# KwadraLampaBT.net
KiCad netlist of a schematic drawn in EAGLE
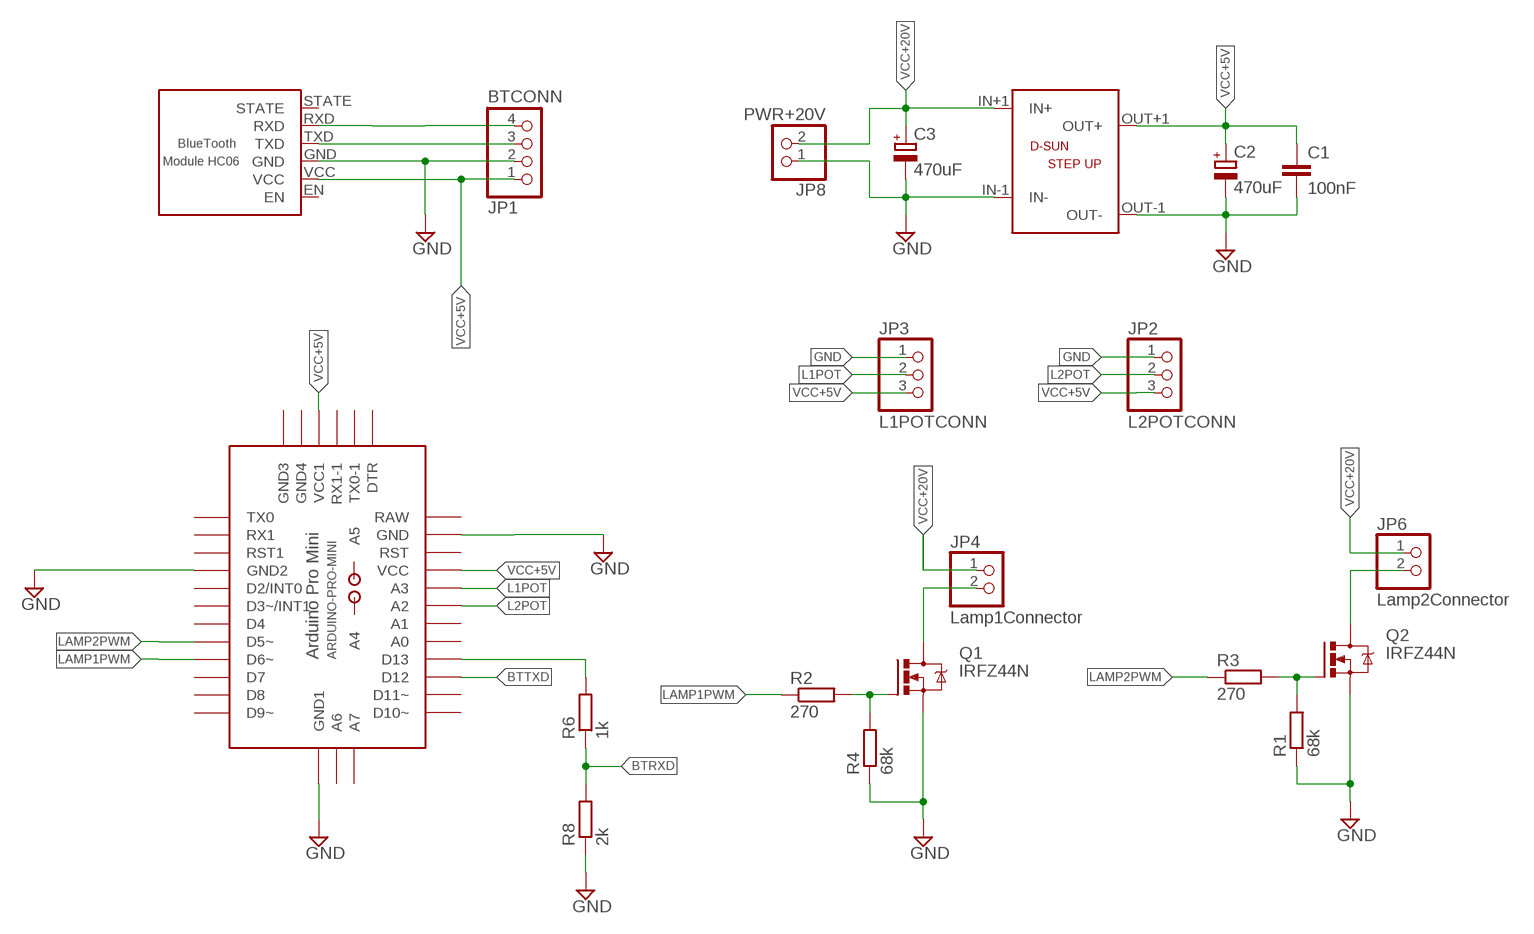
[diagram p0: schematic, sheet 1]

(export (version "E")
  (design (tool "Eeschema 10.0.6"))
  (components
    (comp (ref "C1")
      (value "100nF")
      (footprint "eagle-import:C025-025X050")
      (libsource (lib "eagle-import") (part "C_CERAMIC_2.5X50"))
    )
    (comp (ref "C2")
      (value "470uF")
      (footprint "eagle-import:C_E_R5-FI13_ELECTROLYTIC")
      (libsource (lib "eagle-import") (part "C_ELECTROLYTIC_3"))
    )
    (comp (ref "C3")
      (value "470uF")
      (footprint "eagle-import:C_E_R5-FI13_ELECTROLYTIC")
      (libsource (lib "eagle-import") (part "C_ELECTROLYTIC_3"))
    )
    (comp (ref "IC1")
      (value "HC06")
      (footprint "eagle-import:HC06")
      (libsource (lib "eagle-import") (part "HC06"))
    )
    (comp (ref "JP1")
      (value "BTCONN")
      (footprint "eagle-import:1X04")
      (libsource (lib "eagle-import") (part "PINHD-1X4"))
    )
    (comp (ref "JP2")
      (value "L2POTCONN")
      (footprint "eagle-import:1X03")
      (libsource (lib "eagle-import") (part "PINHD-1X3"))
    )
    (comp (ref "JP3")
      (value "L1POTCONN")
      (footprint "eagle-import:1X03")
      (libsource (lib "eagle-import") (part "PINHD-1X3"))
    )
    (comp (ref "JP4")
      (value "Lamp1Connector")
      (footprint "eagle-import:1X02")
      (libsource (lib "eagle-import") (part "PINHD-1X2"))
    )
    (comp (ref "JP6")
      (value "Lamp2Connector")
      (footprint "eagle-import:1X02")
      (libsource (lib "eagle-import") (part "PINHD-1X2"))
    )
    (comp (ref "JP8")
      (value "PWR+20V")
      (footprint "eagle-import:1X02")
      (libsource (lib "eagle-import") (part "PINHD-1X2"))
    )
    (comp (ref "Q1")
      (value "IRFZ44N")
      (footprint "eagle-import:TO220AB-GDS-VERT")
      (libsource (lib "eagle-import") (part "IRFZ44NVERT"))
    )
    (comp (ref "Q2")
      (value "IRFZ44N")
      (footprint "eagle-import:TO220AB-GDS-VERT")
      (libsource (lib "eagle-import") (part "IRFZ44NVERT"))
    )
    (comp (ref "R1")
      (value "68k")
      (footprint "eagle-import:SMD1206")
      (libsource (lib "eagle-import") (part "R_SMD1206"))
    )
    (comp (ref "R2")
      (value "270")
      (footprint "eagle-import:SMD1206")
      (libsource (lib "eagle-import") (part "R_SMD1206"))
    )
    (comp (ref "R3")
      (value "270")
      (footprint "eagle-import:SMD1206")
      (libsource (lib "eagle-import") (part "R_SMD1206"))
    )
    (comp (ref "R4")
      (value "68k")
      (footprint "eagle-import:SMD1206")
      (libsource (lib "eagle-import") (part "R_SMD1206"))
    )
    (comp (ref "R6")
      (value "1k")
      (footprint "eagle-import:SMD1206")
      (libsource (lib "eagle-import") (part "R_SMD1206"))
    )
    (comp (ref "R8")
      (value "2k")
      (footprint "eagle-import:SMD1206")
      (libsource (lib "eagle-import") (part "R_SMD1206"))
    )
    (comp (ref "U$1")
      (value "ARDUINO-PRO-MINI")
      (footprint "eagle-import:ARDUINO-PRO-MINI")
      (libsource (lib "eagle-import") (part "ARDUINO-PRO-MINI"))
    )
    (comp (ref "U$2")
      (value "STEPUP_D-SUN")
      (footprint "eagle-import:STEPUP_D-SUN")
      (libsource (lib "eagle-import") (part "STEPUP_D-SUN"))
    )
  )
  (nets
    (net (code "1") (name "BTRXD") (class "Default")
      (node (ref "IC1") (pin "RXD") (pinfunction "RXD_RXD") (pintype "input"))
      (node (ref "JP1") (pin "4") (pinfunction "4_4") (pintype "passive"))
      (node (ref "R6") (pin "1") (pinfunction "1_1") (pintype "passive"))
      (node (ref "R8") (pin "2") (pinfunction "2_2") (pintype "passive"))
    )
    (net (code "2") (name "BTTXD") (class "Default")
      (node (ref "IC1") (pin "TXD") (pinfunction "TXD_TXD") (pintype "output"))
      (node (ref "JP1") (pin "3") (pinfunction "3_3") (pintype "passive"))
      (node (ref "U$1") (pin "D12") (pinfunction "D12_D12") (pintype "bidirectional"))
    )
    (net (code "3") (name "GND") (class "Default")
      (node (ref "C1") (pin "2") (pinfunction "2_2") (pintype "passive"))
      (node (ref "C2") (pin "-") (pinfunction "-_-") (pintype "passive"))
      (node (ref "C3") (pin "-") (pinfunction "-_-") (pintype "passive"))
      (node (ref "IC1") (pin "GND") (pinfunction "GND_GND") (pintype "power_in"))
      (node (ref "JP1") (pin "2") (pinfunction "2_2") (pintype "passive"))
      (node (ref "JP2") (pin "1") (pinfunction "1_1") (pintype "passive"))
      (node (ref "JP3") (pin "1") (pinfunction "1_1") (pintype "passive"))
      (node (ref "JP8") (pin "1") (pinfunction "1_1") (pintype "passive"))
      (node (ref "Q1") (pin "S") (pinfunction "S_S") (pintype "passive"))
      (node (ref "Q2") (pin "S") (pinfunction "S_S") (pintype "passive"))
      (node (ref "R1") (pin "1") (pinfunction "1_1") (pintype "passive"))
      (node (ref "R4") (pin "1") (pinfunction "1_1") (pintype "passive"))
      (node (ref "R8") (pin "1") (pinfunction "1_1") (pintype "passive"))
      (node (ref "U$1") (pin "GND") (pinfunction "GND_GND") (pintype "power_in"))
      (node (ref "U$1") (pin "GND1") (pinfunction "GND1_GND1") (pintype "power_in"))
      (node (ref "U$1") (pin "GND2") (pinfunction "GND2_GND2") (pintype "power_in"))
      (node (ref "U$2") (pin "IN-1") (pinfunction "IN-_IN-1") (pintype "bidirectional"))
      (node (ref "U$2") (pin "OUT-1") (pinfunction "OUT-_OUT-1") (pintype "bidirectional"))
    )
    (net (code "4") (name "L1POT") (class "Default")
      (node (ref "JP3") (pin "2") (pinfunction "2_2") (pintype "passive"))
      (node (ref "U$1") (pin "A3") (pinfunction "A3_A3") (pintype "bidirectional"))
    )
    (net (code "5") (name "L2POT") (class "Default")
      (node (ref "JP2") (pin "2") (pinfunction "2_2") (pintype "passive"))
      (node (ref "U$1") (pin "A2") (pinfunction "A2_A2") (pintype "bidirectional"))
    )
    (net (code "6") (name "LAMP1PWM") (class "Default")
      (node (ref "R2") (pin "1") (pinfunction "1_1") (pintype "passive"))
      (node (ref "U$1") (pin "D6") (pinfunction "D6~{}_D6") (pintype "bidirectional"))
    )
    (net (code "7") (name "LAMP2PWM") (class "Default")
      (node (ref "R3") (pin "1") (pinfunction "1_1") (pintype "passive"))
      (node (ref "U$1") (pin "D5") (pinfunction "D5~{}_D5") (pintype "bidirectional"))
    )
    (net (code "8") (name "Net-(JP4-Pad2)") (class "Default")
      (node (ref "JP4") (pin "2") (pinfunction "2_2") (pintype "passive"))
      (node (ref "Q1") (pin "D") (pinfunction "D_D") (pintype "passive"))
    )
    (net (code "9") (name "Net-(JP6-Pad2)") (class "Default")
      (node (ref "JP6") (pin "2") (pinfunction "2_2") (pintype "passive"))
      (node (ref "Q2") (pin "D") (pinfunction "D_D") (pintype "passive"))
    )
    (net (code "10") (name "Net-(Q1-PadG)") (class "Default")
      (node (ref "Q1") (pin "G") (pinfunction "G_G") (pintype "passive"))
      (node (ref "R2") (pin "2") (pinfunction "2_2") (pintype "passive"))
      (node (ref "R4") (pin "2") (pinfunction "2_2") (pintype "passive"))
    )
    (net (code "11") (name "Net-(Q2-PadG)") (class "Default")
      (node (ref "Q2") (pin "G") (pinfunction "G_G") (pintype "passive"))
      (node (ref "R1") (pin "2") (pinfunction "2_2") (pintype "passive"))
      (node (ref "R3") (pin "2") (pinfunction "2_2") (pintype "passive"))
    )
    (net (code "12") (name "Net-(R6-Pad2)") (class "Default")
      (node (ref "R6") (pin "2") (pinfunction "2_2") (pintype "passive"))
      (node (ref "U$1") (pin "D13") (pinfunction "D13_D13") (pintype "bidirectional"))
    )
    (net (code "13") (name "VCC+5V") (class "Default")
      (node (ref "C1") (pin "1") (pinfunction "1_1") (pintype "passive"))
      (node (ref "C2") (pin "+") (pinfunction "+_+") (pintype "passive"))
      (node (ref "IC1") (pin "VCC") (pinfunction "VCC_VCC") (pintype "power_in"))
      (node (ref "JP1") (pin "1") (pinfunction "1_1") (pintype "passive"))
      (node (ref "JP2") (pin "3") (pinfunction "3_3") (pintype "passive"))
      (node (ref "JP3") (pin "3") (pinfunction "3_3") (pintype "passive"))
      (node (ref "U$1") (pin "VCC") (pinfunction "VCC_VCC") (pintype "power_in"))
      (node (ref "U$1") (pin "VCC1") (pinfunction "VCC1_VCC1") (pintype "power_in"))
      (node (ref "U$2") (pin "OUT+1") (pinfunction "OUT+_OUT+1") (pintype "bidirectional"))
    )
    (net (code "14") (name "VCC+20V") (class "Default")
      (node (ref "C3") (pin "+") (pinfunction "+_+") (pintype "passive"))
      (node (ref "JP4") (pin "1") (pinfunction "1_1") (pintype "passive"))
      (node (ref "JP6") (pin "1") (pinfunction "1_1") (pintype "passive"))
      (node (ref "JP8") (pin "2") (pinfunction "2_2") (pintype "passive"))
      (node (ref "U$2") (pin "IN+1") (pinfunction "IN+_IN+1") (pintype "bidirectional"))
    )
    (net (code "15") (name "unconnected-(IC1-PadEN)") (class "Default")
      (node (ref "IC1") (pin "EN") (pinfunction "EN_EN") (pintype "input"))
    )
    (net (code "16") (name "unconnected-(IC1-PadSTATE)") (class "Default")
      (node (ref "IC1") (pin "STATE") (pinfunction "STATE_STATE") (pintype "output"))
    )
    (net (code "17") (name "unconnected-(U$1-D2{slash}INT0-PadD2)") (class "Default")
      (node (ref "U$1") (pin "D2") (pinfunction "D2/INT0_D2") (pintype "bidirectional"))
    )
    (net (code "18") (name "unconnected-(U$1-D3~{{slash}INT1}-PadD3)") (class "Default")
      (node (ref "U$1") (pin "D3") (pinfunction "D3~{/INT1}_D3") (pintype "bidirectional"))
    )
    (net (code "19") (name "unconnected-(U$1-D9~{}-PadD9)") (class "Default")
      (node (ref "U$1") (pin "D9") (pinfunction "D9~{}_D9") (pintype "bidirectional"))
    )
    (net (code "20") (name "unconnected-(U$1-D10~{}-PadD10)") (class "Default")
      (node (ref "U$1") (pin "D10") (pinfunction "D10~{}_D10") (pintype "bidirectional"))
    )
    (net (code "21") (name "unconnected-(U$1-D11~{}-PadD11)") (class "Default")
      (node (ref "U$1") (pin "D11") (pinfunction "D11~{}_D11") (pintype "bidirectional"))
    )
    (net (code "22") (name "unconnected-(U$1-PadA0)") (class "Default")
      (node (ref "U$1") (pin "A0") (pinfunction "A0_A0") (pintype "bidirectional"))
    )
    (net (code "23") (name "unconnected-(U$1-PadA1)") (class "Default")
      (node (ref "U$1") (pin "A1") (pinfunction "A1_A1") (pintype "bidirectional"))
    )
    (net (code "24") (name "unconnected-(U$1-PadA4)") (class "Default")
      (node (ref "U$1") (pin "A4") (pinfunction "A4_A4") (pintype "bidirectional"))
    )
    (net (code "25") (name "unconnected-(U$1-PadA5)") (class "Default")
      (node (ref "U$1") (pin "A5") (pinfunction "A5_A5") (pintype "bidirectional"))
    )
    (net (code "26") (name "unconnected-(U$1-PadA6)") (class "Default")
      (node (ref "U$1") (pin "A6") (pinfunction "A6_A6") (pintype "bidirectional"))
    )
    (net (code "27") (name "unconnected-(U$1-PadA7)") (class "Default")
      (node (ref "U$1") (pin "A7") (pinfunction "A7_A7") (pintype "bidirectional"))
    )
    (net (code "28") (name "unconnected-(U$1-PadD4)") (class "Default")
      (node (ref "U$1") (pin "D4") (pinfunction "D4_D4") (pintype "bidirectional"))
    )
    (net (code "29") (name "unconnected-(U$1-PadD7)") (class "Default")
      (node (ref "U$1") (pin "D7") (pinfunction "D7_D7") (pintype "bidirectional"))
    )
    (net (code "30") (name "unconnected-(U$1-PadD8)") (class "Default")
      (node (ref "U$1") (pin "D8") (pinfunction "D8_D8") (pintype "bidirectional"))
    )
    (net (code "31") (name "unconnected-(U$1-PadDTR)") (class "Default")
      (node (ref "U$1") (pin "DTR") (pinfunction "DTR_DTR") (pintype "bidirectional"))
    )
    (net (code "32") (name "unconnected-(U$1-PadGND3)") (class "Default")
      (node (ref "U$1") (pin "GND3") (pinfunction "GND3_GND3") (pintype "bidirectional"))
    )
    (net (code "33") (name "unconnected-(U$1-PadGND4)") (class "Default")
      (node (ref "U$1") (pin "GND4") (pinfunction "GND4_GND4") (pintype "bidirectional"))
    )
    (net (code "34") (name "unconnected-(U$1-PadRST)") (class "Default")
      (node (ref "U$1") (pin "RST") (pinfunction "RST_RST") (pintype "bidirectional"))
    )
    (net (code "35") (name "unconnected-(U$1-PadRST1)") (class "Default")
      (node (ref "U$1") (pin "RST1") (pinfunction "RST1_RST1") (pintype "bidirectional"))
    )
    (net (code "36") (name "unconnected-(U$1-PadRX1)") (class "Default")
      (node (ref "U$1") (pin "RX1") (pinfunction "RX1_RX1") (pintype "bidirectional"))
    )
    (net (code "37") (name "unconnected-(U$1-PadRX1-1)") (class "Default")
      (node (ref "U$1") (pin "RX1-1") (pinfunction "RX1-1_RX1-1") (pintype "bidirectional"))
    )
    (net (code "38") (name "unconnected-(U$1-PadTX0)") (class "Default")
      (node (ref "U$1") (pin "TX0") (pinfunction "TX0_TX0") (pintype "bidirectional"))
    )
    (net (code "39") (name "unconnected-(U$1-PadTX0-1)") (class "Default")
      (node (ref "U$1") (pin "TX0-1") (pinfunction "TX0-1_TX0-1") (pintype "bidirectional"))
    )
    (net (code "40") (name "unconnected-(U$1-RAW-PadRAWVOLTAGE)") (class "Default")
      (node (ref "U$1") (pin "RAWVOLTAGE") (pinfunction "RAW_RAWVOLTAGE") (pintype "bidirectional"))
    )
  )
)
